# DMX_RX.net
KiCad netlist of a schematic drawn in EAGLE
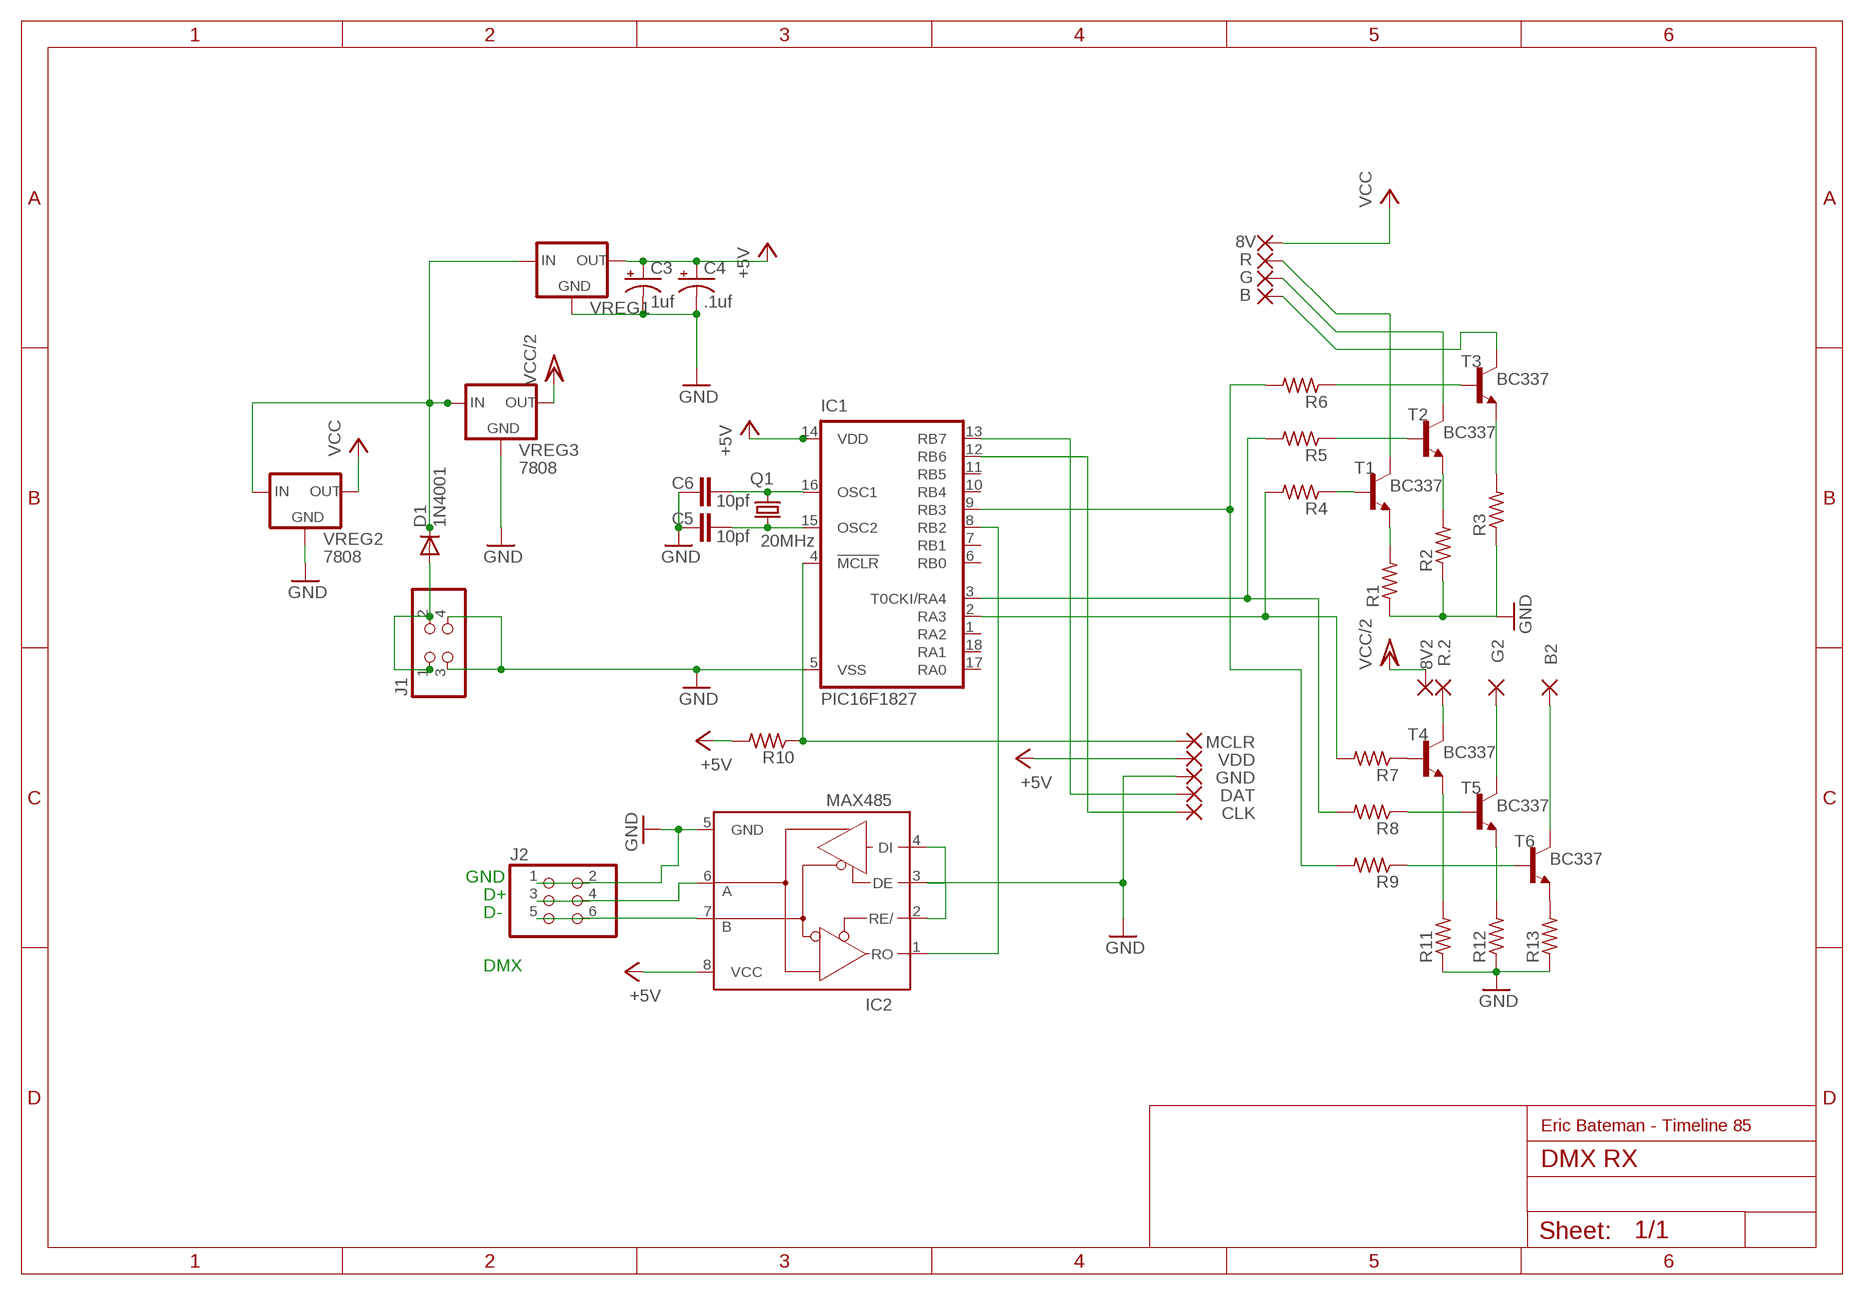
[diagram p0: schematic, sheet 1]

(export (version "E")
  (design (tool "Eeschema 10.0.6"))
  (components
    (comp (ref "8V")
      (value "2,15/1,0")
      (footprint "eagle-import:2,15_1,0")
      (libsource (lib "eagle-import") (part "2,15/1,0"))
    )
    (comp (ref "8V2")
      (value "2,15/1,0")
      (footprint "eagle-import:2,15_1,0")
      (libsource (lib "eagle-import") (part "2,15/1,0"))
    )
    (comp (ref "B")
      (value "2,15/1,0")
      (footprint "eagle-import:2,15_1,0")
      (libsource (lib "eagle-import") (part "2,15/1,0"))
    )
    (comp (ref "B2")
      (value "2,15/1,0")
      (footprint "eagle-import:2,15_1,0")
      (libsource (lib "eagle-import") (part "2,15/1,0"))
    )
    (comp (ref "C3")
      (value "1uf")
      (footprint "eagle-import:E2,5-7")
      (libsource (lib "eagle-import") (part "CPOL-USE2.5-7"))
    )
    (comp (ref "C4")
      (value ".1uf")
      (footprint "eagle-import:E2,5-7")
      (libsource (lib "eagle-import") (part "CPOL-USE2.5-7"))
    )
    (comp (ref "C5")
      (value "10pf")
      (footprint "eagle-import:C5B3.5")
      (libsource (lib "eagle-import") (part "C5/3.5"))
    )
    (comp (ref "C6")
      (value "10pf")
      (footprint "eagle-import:C5B3.5")
      (libsource (lib "eagle-import") (part "C5/3.5"))
    )
    (comp (ref "CLK")
      (value "1,6/0,8")
      (footprint "eagle-import:1,6_0,8")
      (libsource (lib "eagle-import") (part "1,6/0,8"))
    )
    (comp (ref "D1")
      (value "1N4001")
      (footprint "eagle-import:DIODE-1N4001")
      (libsource (lib "eagle-import") (part "DIODEPTH"))
    )
    (comp (ref "DAT")
      (value "1,6/0,8")
      (footprint "eagle-import:1,6_0,8")
      (libsource (lib "eagle-import") (part "1,6/0,8"))
    )
    (comp (ref "G")
      (value "2,15/1,0")
      (footprint "eagle-import:2,15_1,0")
      (libsource (lib "eagle-import") (part "2,15/1,0"))
    )
    (comp (ref "G2")
      (value "2,15/1,0")
      (footprint "eagle-import:2,15_1,0")
      (libsource (lib "eagle-import") (part "2,15/1,0"))
    )
    (comp (ref "GND")
      (value "1,6/0,8")
      (footprint "eagle-import:1,6_0,8")
      (libsource (lib "eagle-import") (part "1,6/0,8"))
    )
    (comp (ref "IC1")
      (value "PIC16F1827")
      (footprint "eagle-import:DIL18")
      (fields (field (name "MPN") "PIC16F83-04/P"))
      (libsource (lib "eagle-import") (part "PIC16F8P3"))
    )
    (comp (ref "IC2")
      (value "MAX485")
      (footprint "eagle-import:DIL08")
      (libsource (lib "eagle-import") (part "MAX34PA68C"))
    )
    (comp (ref "J1")
      (value "PINHD-2X2/90")
      (footprint "eagle-import:2X02_90")
      (libsource (lib "eagle-import") (part "PINHD-2X2/90"))
    )
    (comp (ref "J2")
      (value "PINHD-2X3/90")
      (footprint "eagle-import:2X03_90")
      (libsource (lib "eagle-import") (part "PINHD-2X3/90"))
    )
    (comp (ref "MCLR")
      (value "1,6/0,8")
      (footprint "eagle-import:1,6_0,8")
      (libsource (lib "eagle-import") (part "1,6/0,8"))
    )
    (comp (ref "Q1")
      (value "20MHz")
      (footprint "eagle-import:HC49_S")
      (libsource (lib "eagle-import") (part "CRYSTALHC49S"))
    )
    (comp (ref "R")
      (value "2,15/1,0")
      (footprint "eagle-import:2,15_1,0")
      (libsource (lib "eagle-import") (part "2,15/1,0"))
    )
    (comp (ref "R.2")
      (value "2,15/1,0")
      (footprint "eagle-import:2,15_1,0")
      (libsource (lib "eagle-import") (part "2,15/1,0"))
    )
    (comp (ref "R1")
      (value "R-US_0411/12")
      (footprint "eagle-import:0411_12")
      (libsource (lib "eagle-import") (part "R-US_0411/12"))
    )
    (comp (ref "R2")
      (value "R-US_0411/12")
      (footprint "eagle-import:0411_12")
      (libsource (lib "eagle-import") (part "R-US_0411/12"))
    )
    (comp (ref "R3")
      (value "R-US_0411/12")
      (footprint "eagle-import:0411_12")
      (libsource (lib "eagle-import") (part "R-US_0411/12"))
    )
    (comp (ref "R4")
      (value "R-US_0204/7")
      (footprint "eagle-import:0204_7")
      (libsource (lib "eagle-import") (part "R-US_0204/7"))
    )
    (comp (ref "R5")
      (value "R-US_0204/7")
      (footprint "eagle-import:0204_7")
      (libsource (lib "eagle-import") (part "R-US_0204/7"))
    )
    (comp (ref "R6")
      (value "R-US_0204/7")
      (footprint "eagle-import:0204_7")
      (libsource (lib "eagle-import") (part "R-US_0204/7"))
    )
    (comp (ref "R7")
      (value "R-US_0204/7")
      (footprint "eagle-import:0204_7")
      (libsource (lib "eagle-import") (part "R-US_0204/7"))
    )
    (comp (ref "R8")
      (value "R-US_0204/7")
      (footprint "eagle-import:0204_7")
      (libsource (lib "eagle-import") (part "R-US_0204/7"))
    )
    (comp (ref "R9")
      (value "R-US_0204/7")
      (footprint "eagle-import:0204_7")
      (libsource (lib "eagle-import") (part "R-US_0204/7"))
    )
    (comp (ref "R10")
      (value "R-US_0204/7")
      (footprint "eagle-import:0204_7")
      (libsource (lib "eagle-import") (part "R-US_0204/7"))
    )
    (comp (ref "R11")
      (value "R-US_0411/12")
      (footprint "eagle-import:0411_12")
      (libsource (lib "eagle-import") (part "R-US_0411/12"))
    )
    (comp (ref "R12")
      (value "R-US_0411/12")
      (footprint "eagle-import:0411_12")
      (libsource (lib "eagle-import") (part "R-US_0411/12"))
    )
    (comp (ref "R13")
      (value "R-US_0411/12")
      (footprint "eagle-import:0411_12")
      (libsource (lib "eagle-import") (part "R-US_0411/12"))
    )
    (comp (ref "T1")
      (value "BC337")
      (footprint "eagle-import:TO92")
      (libsource (lib "eagle-import") (part "BC337"))
    )
    (comp (ref "T2")
      (value "BC337")
      (footprint "eagle-import:TO92")
      (libsource (lib "eagle-import") (part "BC337"))
    )
    (comp (ref "T3")
      (value "BC337")
      (footprint "eagle-import:TO92")
      (libsource (lib "eagle-import") (part "BC337"))
    )
    (comp (ref "T4")
      (value "BC337")
      (footprint "eagle-import:TO92")
      (libsource (lib "eagle-import") (part "BC337"))
    )
    (comp (ref "T5")
      (value "BC337")
      (footprint "eagle-import:TO92")
      (libsource (lib "eagle-import") (part "BC337"))
    )
    (comp (ref "T6")
      (value "BC337")
      (footprint "eagle-import:TO92")
      (libsource (lib "eagle-import") (part "BC337"))
    )
    (comp (ref "VDD")
      (value "1,6/0,8")
      (footprint "eagle-import:1,6_0,8")
      (libsource (lib "eagle-import") (part "1,6/0,8"))
    )
    (comp (ref "VREG1")
      (value "78LXX")
      (footprint "eagle-import:78LXX")
      (libsource (lib "eagle-import") (part "78LXX"))
    )
    (comp (ref "VREG2")
      (value "7808")
      (footprint "eagle-import:78XXS")
      (libsource (lib "eagle-import") (part "78XXS"))
    )
    (comp (ref "VREG3")
      (value "7808")
      (footprint "eagle-import:78XXS")
      (libsource (lib "eagle-import") (part "78XXS"))
    )
  )
  (nets
    (net (code "1") (name "+5V") (class "Default")
      (node (ref "C3") (pin "+") (pinfunction "+_+") (pintype "passive"))
      (node (ref "C4") (pin "+") (pinfunction "+_+") (pintype "passive"))
      (node (ref "IC1") (pin "14") (pinfunction "VDD_14") (pintype "power_in"))
      (node (ref "IC2") (pin "8") (pinfunction "VCC_8") (pintype "power_in"))
      (node (ref "R10") (pin "2") (pinfunction "2_2") (pintype "passive"))
      (node (ref "VDD") (pin "1") (pinfunction "P_1") (pintype "passive"))
      (node (ref "VREG1") (pin "OUT") (pinfunction "OUT_OUT") (pintype "passive"))
    )
    (net (code "2") (name "GND") (class "Default")
      (node (ref "C3") (pin "-") (pinfunction "-_-") (pintype "passive"))
      (node (ref "C4") (pin "-") (pinfunction "-_-") (pintype "passive"))
      (node (ref "C5") (pin "2") (pinfunction "2_2") (pintype "passive"))
      (node (ref "C6") (pin "2") (pinfunction "2_2") (pintype "passive"))
      (node (ref "GND") (pin "1") (pinfunction "P_1") (pintype "passive"))
      (node (ref "IC1") (pin "5") (pinfunction "VSS_5") (pintype "power_in"))
      (node (ref "IC2") (pin "2") (pinfunction "RE/_2") (pintype "input"))
      (node (ref "IC2") (pin "3") (pinfunction "DE_3") (pintype "input"))
      (node (ref "IC2") (pin "4") (pinfunction "DI_4") (pintype "input"))
      (node (ref "IC2") (pin "5") (pinfunction "GND_5") (pintype "power_in"))
      (node (ref "J1") (pin "3") (pinfunction "3_3") (pintype "passive"))
      (node (ref "J1") (pin "4") (pinfunction "4_4") (pintype "passive"))
      (node (ref "J2") (pin "1") (pinfunction "1_1") (pintype "passive"))
      (node (ref "J2") (pin "2") (pinfunction "2_2") (pintype "passive"))
      (node (ref "R1") (pin "1") (pinfunction "1_1") (pintype "passive"))
      (node (ref "R11") (pin "1") (pinfunction "1_1") (pintype "passive"))
      (node (ref "R12") (pin "1") (pinfunction "1_1") (pintype "passive"))
      (node (ref "R13") (pin "1") (pinfunction "1_1") (pintype "passive"))
      (node (ref "R2") (pin "1") (pinfunction "1_1") (pintype "passive"))
      (node (ref "R3") (pin "1") (pinfunction "1_1") (pintype "passive"))
      (node (ref "VREG1") (pin "GND") (pinfunction "GND_GND") (pintype "input"))
      (node (ref "VREG2") (pin "GND") (pinfunction "GND_GND") (pintype "input"))
      (node (ref "VREG3") (pin "GND") (pinfunction "GND_GND") (pintype "input"))
    )
    (net (code "3") (name "Net-(B-P)") (class "Default")
      (node (ref "B") (pin "1") (pinfunction "P_1") (pintype "passive"))
      (node (ref "T3") (pin "3") (pinfunction "C_3") (pintype "passive"))
    )
    (net (code "4") (name "Net-(B2-P)") (class "Default")
      (node (ref "B2") (pin "1") (pinfunction "P_1") (pintype "passive"))
      (node (ref "T6") (pin "3") (pinfunction "C_3") (pintype "passive"))
    )
    (net (code "5") (name "Net-(CLK-P)") (class "Default")
      (node (ref "CLK") (pin "1") (pinfunction "P_1") (pintype "passive"))
      (node (ref "IC1") (pin "12") (pinfunction "RB6_12") (pintype "bidirectional"))
    )
    (net (code "6") (name "Net-(D1-PadA)") (class "Default")
      (node (ref "D1") (pin "A") (pinfunction "A_A") (pintype "passive"))
      (node (ref "J1") (pin "1") (pinfunction "1_1") (pintype "passive"))
      (node (ref "J1") (pin "2") (pinfunction "2_2") (pintype "passive"))
    )
    (net (code "7") (name "Net-(D1-PadC)") (class "Default")
      (node (ref "D1") (pin "C") (pinfunction "C_C") (pintype "passive"))
      (node (ref "VREG1") (pin "IN") (pinfunction "IN_IN") (pintype "input"))
      (node (ref "VREG2") (pin "IN") (pinfunction "IN_IN") (pintype "input"))
      (node (ref "VREG3") (pin "IN") (pinfunction "IN_IN") (pintype "input"))
    )
    (net (code "8") (name "Net-(DAT-P)") (class "Default")
      (node (ref "DAT") (pin "1") (pinfunction "P_1") (pintype "passive"))
      (node (ref "IC1") (pin "13") (pinfunction "RB7_13") (pintype "bidirectional"))
    )
    (net (code "9") (name "Net-(G-P)") (class "Default")
      (node (ref "G") (pin "1") (pinfunction "P_1") (pintype "passive"))
      (node (ref "T2") (pin "3") (pinfunction "C_3") (pintype "passive"))
    )
    (net (code "10") (name "Net-(G2-P)") (class "Default")
      (node (ref "G2") (pin "1") (pinfunction "P_1") (pintype "passive"))
      (node (ref "T5") (pin "3") (pinfunction "C_3") (pintype "passive"))
    )
    (net (code "11") (name "Net-(IC1-OSC1)") (class "Default")
      (node (ref "C6") (pin "1") (pinfunction "1_1") (pintype "passive"))
      (node (ref "IC1") (pin "16") (pinfunction "OSC1_16") (pintype "input"))
      (node (ref "Q1") (pin "1") (pinfunction "1_1") (pintype "passive"))
    )
    (net (code "12") (name "Net-(IC1-OSC2)") (class "Default")
      (node (ref "C5") (pin "1") (pinfunction "1_1") (pintype "passive"))
      (node (ref "IC1") (pin "15") (pinfunction "OSC2_15") (pintype "output"))
      (node (ref "Q1") (pin "2") (pinfunction "2_2") (pintype "passive"))
    )
    (net (code "13") (name "Net-(IC1-RA3)") (class "Default")
      (node (ref "IC1") (pin "2") (pinfunction "RA3_2") (pintype "bidirectional"))
      (node (ref "R4") (pin "2") (pinfunction "2_2") (pintype "passive"))
      (node (ref "R7") (pin "2") (pinfunction "2_2") (pintype "passive"))
    )
    (net (code "14") (name "Net-(IC1-RB2)") (class "Default")
      (node (ref "IC1") (pin "8") (pinfunction "RB2_8") (pintype "bidirectional"))
      (node (ref "IC2") (pin "1") (pinfunction "RO_1") (pintype "output"))
    )
    (net (code "15") (name "Net-(IC1-RB3)") (class "Default")
      (node (ref "IC1") (pin "9") (pinfunction "RB3_9") (pintype "bidirectional"))
      (node (ref "R6") (pin "2") (pinfunction "2_2") (pintype "passive"))
      (node (ref "R9") (pin "2") (pinfunction "2_2") (pintype "passive"))
    )
    (net (code "16") (name "Net-(IC1-T0CKI{slash}RA4)") (class "Default")
      (node (ref "IC1") (pin "3") (pinfunction "T0CKI/RA4_3") (pintype "bidirectional"))
      (node (ref "R5") (pin "2") (pinfunction "2_2") (pintype "passive"))
      (node (ref "R8") (pin "2") (pinfunction "2_2") (pintype "passive"))
    )
    (net (code "17") (name "Net-(IC1-~{MCLR})") (class "Default")
      (node (ref "IC1") (pin "4") (pinfunction "~{MCLR}_4") (pintype "input"))
      (node (ref "MCLR") (pin "1") (pinfunction "P_1") (pintype "passive"))
      (node (ref "R10") (pin "1") (pinfunction "1_1") (pintype "passive"))
    )
    (net (code "18") (name "Net-(IC2-A)") (class "Default")
      (node (ref "IC2") (pin "6") (pinfunction "A_6") (pintype "passive"))
      (node (ref "J2") (pin "3") (pinfunction "3_3") (pintype "passive"))
      (node (ref "J2") (pin "4") (pinfunction "4_4") (pintype "passive"))
    )
    (net (code "19") (name "Net-(IC2-B)") (class "Default")
      (node (ref "IC2") (pin "7") (pinfunction "B_7") (pintype "passive"))
      (node (ref "J2") (pin "5") (pinfunction "5_5") (pintype "passive"))
      (node (ref "J2") (pin "6") (pinfunction "6_6") (pintype "passive"))
    )
    (net (code "20") (name "Net-(R-P)") (class "Default")
      (node (ref "R") (pin "1") (pinfunction "P_1") (pintype "passive"))
      (node (ref "T1") (pin "3") (pinfunction "C_3") (pintype "passive"))
    )
    (net (code "21") (name "Net-(R.2-P)") (class "Default")
      (node (ref "R.2") (pin "1") (pinfunction "P_1") (pintype "passive"))
      (node (ref "T4") (pin "3") (pinfunction "C_3") (pintype "passive"))
    )
    (net (code "22") (name "Net-(T1-B)") (class "Default")
      (node (ref "R4") (pin "1") (pinfunction "1_1") (pintype "passive"))
      (node (ref "T1") (pin "2") (pinfunction "B_2") (pintype "passive"))
    )
    (net (code "23") (name "Net-(T1-E)") (class "Default")
      (node (ref "R1") (pin "2") (pinfunction "2_2") (pintype "passive"))
      (node (ref "T1") (pin "1") (pinfunction "E_1") (pintype "passive"))
    )
    (net (code "24") (name "Net-(T2-B)") (class "Default")
      (node (ref "R5") (pin "1") (pinfunction "1_1") (pintype "passive"))
      (node (ref "T2") (pin "2") (pinfunction "B_2") (pintype "passive"))
    )
    (net (code "25") (name "Net-(T2-E)") (class "Default")
      (node (ref "R2") (pin "2") (pinfunction "2_2") (pintype "passive"))
      (node (ref "T2") (pin "1") (pinfunction "E_1") (pintype "passive"))
    )
    (net (code "26") (name "Net-(T3-B)") (class "Default")
      (node (ref "R6") (pin "1") (pinfunction "1_1") (pintype "passive"))
      (node (ref "T3") (pin "2") (pinfunction "B_2") (pintype "passive"))
    )
    (net (code "27") (name "Net-(T3-E)") (class "Default")
      (node (ref "R3") (pin "2") (pinfunction "2_2") (pintype "passive"))
      (node (ref "T3") (pin "1") (pinfunction "E_1") (pintype "passive"))
    )
    (net (code "28") (name "Net-(T4-B)") (class "Default")
      (node (ref "R7") (pin "1") (pinfunction "1_1") (pintype "passive"))
      (node (ref "T4") (pin "2") (pinfunction "B_2") (pintype "passive"))
    )
    (net (code "29") (name "Net-(T4-E)") (class "Default")
      (node (ref "R11") (pin "2") (pinfunction "2_2") (pintype "passive"))
      (node (ref "T4") (pin "1") (pinfunction "E_1") (pintype "passive"))
    )
    (net (code "30") (name "Net-(T5-B)") (class "Default")
      (node (ref "R8") (pin "1") (pinfunction "1_1") (pintype "passive"))
      (node (ref "T5") (pin "2") (pinfunction "B_2") (pintype "passive"))
    )
    (net (code "31") (name "Net-(T5-E)") (class "Default")
      (node (ref "R12") (pin "2") (pinfunction "2_2") (pintype "passive"))
      (node (ref "T5") (pin "1") (pinfunction "E_1") (pintype "passive"))
    )
    (net (code "32") (name "Net-(T6-B)") (class "Default")
      (node (ref "R9") (pin "1") (pinfunction "1_1") (pintype "passive"))
      (node (ref "T6") (pin "2") (pinfunction "B_2") (pintype "passive"))
    )
    (net (code "33") (name "Net-(T6-E)") (class "Default")
      (node (ref "R13") (pin "2") (pinfunction "2_2") (pintype "passive"))
      (node (ref "T6") (pin "1") (pinfunction "E_1") (pintype "passive"))
    )
    (net (code "34") (name "VCC") (class "Default")
      (node (ref "8V") (pin "1") (pinfunction "P_1") (pintype "passive"))
      (node (ref "VREG2") (pin "OUT") (pinfunction "OUT_OUT") (pintype "passive"))
    )
    (net (code "35") (name "VCC{slash}2") (class "Default")
      (node (ref "8V2") (pin "1") (pinfunction "P_1") (pintype "passive"))
      (node (ref "VREG3") (pin "OUT") (pinfunction "OUT_OUT") (pintype "passive"))
    )
    (net (code "36") (name "unconnected-(IC1-RA0-Pad17)") (class "Default")
      (node (ref "IC1") (pin "17") (pinfunction "RA0_17") (pintype "bidirectional"))
    )
    (net (code "37") (name "unconnected-(IC1-RA1-Pad18)") (class "Default")
      (node (ref "IC1") (pin "18") (pinfunction "RA1_18") (pintype "bidirectional"))
    )
    (net (code "38") (name "unconnected-(IC1-RA2-Pad1)") (class "Default")
      (node (ref "IC1") (pin "1") (pinfunction "RA2_1") (pintype "bidirectional"))
    )
    (net (code "39") (name "unconnected-(IC1-RB0-Pad6)") (class "Default")
      (node (ref "IC1") (pin "6") (pinfunction "RB0_6") (pintype "bidirectional"))
    )
    (net (code "40") (name "unconnected-(IC1-RB1-Pad7)") (class "Default")
      (node (ref "IC1") (pin "7") (pinfunction "RB1_7") (pintype "bidirectional"))
    )
    (net (code "41") (name "unconnected-(IC1-RB4-Pad10)") (class "Default")
      (node (ref "IC1") (pin "10") (pinfunction "RB4_10") (pintype "bidirectional"))
    )
    (net (code "42") (name "unconnected-(IC1-RB5-Pad11)") (class "Default")
      (node (ref "IC1") (pin "11") (pinfunction "RB5_11") (pintype "bidirectional"))
    )
  )
)
